# 05.net
KiCad netlist of a schematic drawn in Altium Designer
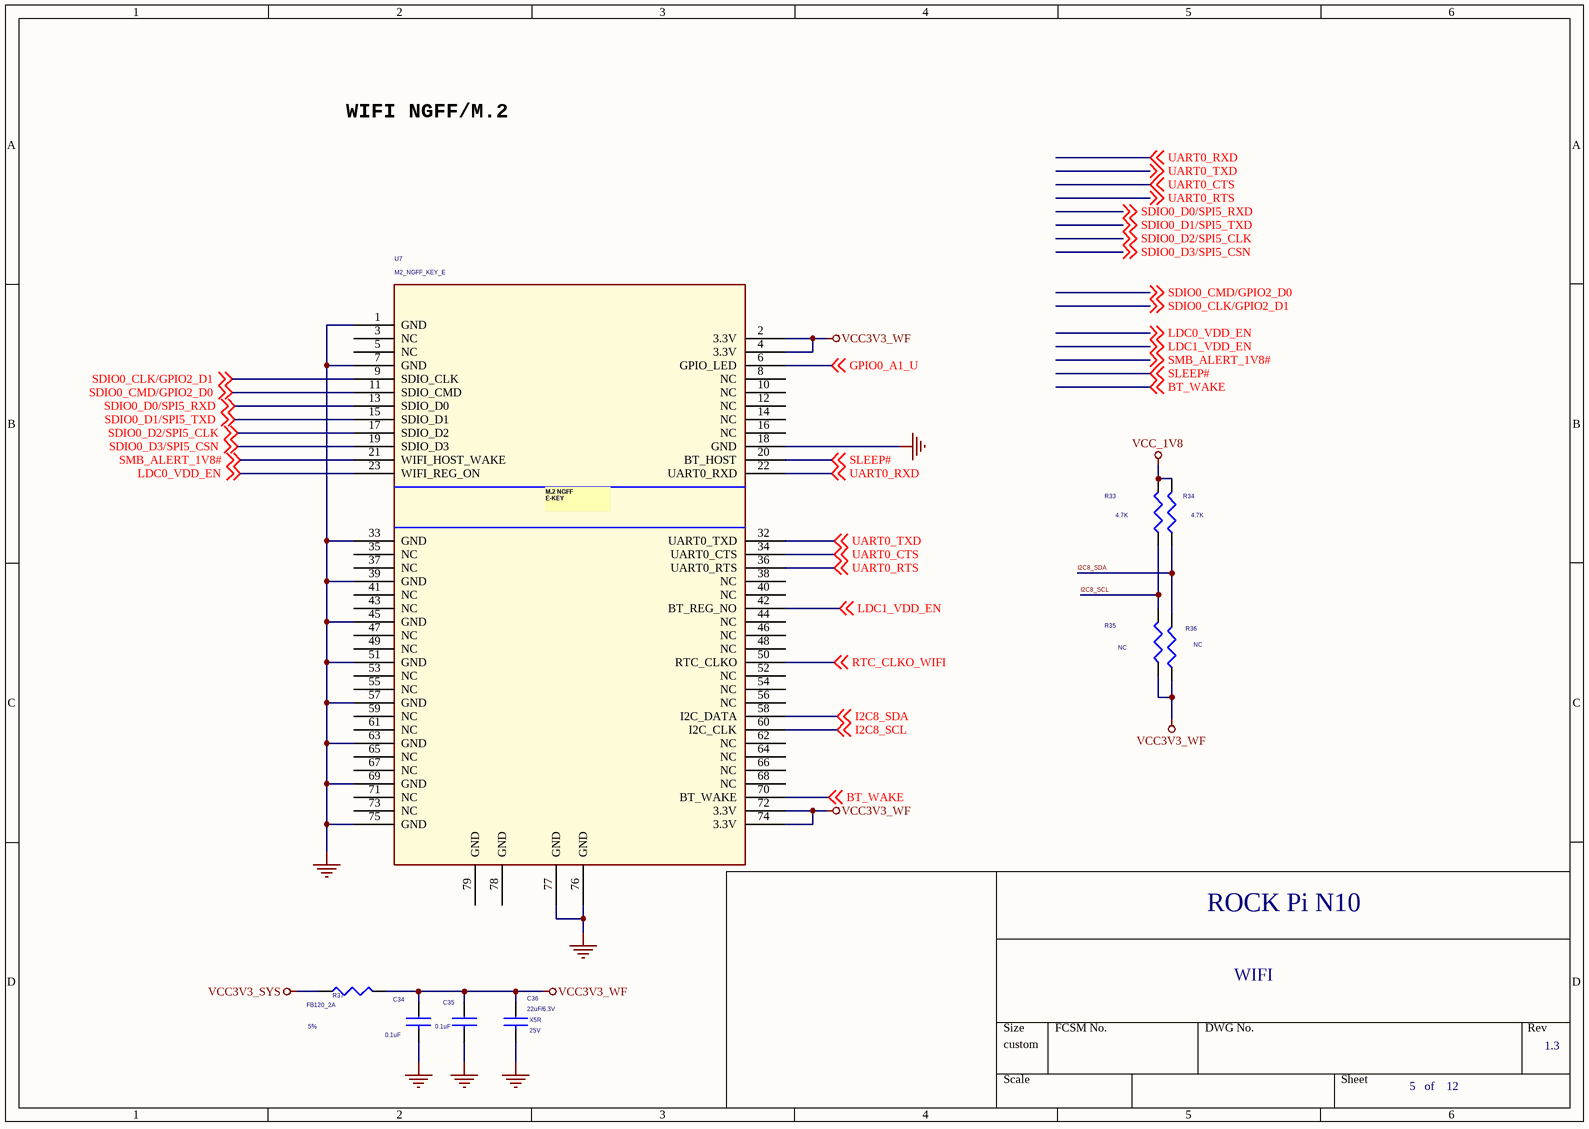
[diagram p0: 05.SchDoc]

(export (version "E")
  (design (tool "Eeschema 10.0.6"))
  (components
    (comp (ref "C34")
      (value "0.1uF")
      (footprint "C0402")
      (description "cap,100.00nF,+/-10%,6.3V,X5R,C0402")
      (fields
        (field (name "VOLTAGE") "16V")
        (field (name "TOLERANCE") "10%")
        (field (name "CREATED BY") "JJJ")
      )
      (libsource (lib "*") (part "CAP NP_2"))
    )
    (comp (ref "C35")
      (value "0.1uF")
      (footprint "C0402")
      (description "cap,100.00nF,+/-10%,6.3V,X5R,C0402")
      (fields
        (field (name "VOLTAGE") "16V")
        (field (name "TOLERANCE") "10%")
        (field (name "CREATED BY") "JJJ")
      )
      (libsource (lib "*") (part "CAP NP_2"))
    )
    (comp (ref "C36")
      (value "22uF/6.3V")
      (footprint "C0805")
      (description "cap,4.70uF,+/-10%,6.3V,X5R,C0603")
      (fields
        (field (name "DIELECTRIC") "X5R")
        (field (name "VOLTAGE") "25V")
        (field (name "MANUFACTURER") "TDK")
        (field (name "TOLERANCE") "10%")
        (field (name "CREATED BY") "JJJ")
      )
      (libsource (lib "*") (part "CAP NP_2"))
    )
    (comp (ref "R33") (value "4.7K") (footprint "R0402") (libsource (lib "*") (part "R_2")))
    (comp (ref "R34") (value "4.7K") (footprint "R0402") (libsource (lib "*") (part "R_2")))
    (comp (ref "R35") (value "NC") (footprint "R0402") (libsource (lib "*") (part "R_2")))
    (comp (ref "R36") (value "NC") (footprint "R0402") (libsource (lib "*") (part "R_2")))
    (comp (ref "R37")
      (value "FB120_2A")
      (footprint "R0402")
      (description "通用厚膜电阻,10K,+/-5%,R0402,1/16W.")
      (fields
        (field (name "TOLERANCE") "5%")
        (field (name "MANUFACTURER") "YAGEO")
        (field (name "CREATED BY") "YTL")
      )
      (libsource (lib "*") (part "RESISTOR_3"))
    )
    (comp (ref "U7")
      (value "M2_NGFF_KEY_E")
      (footprint "M2_NGFF_KEY_E")
      (libsource (lib "*") (part "M_2.2 NGFF EKEY SOCKET"))
    )
  )
  (nets
    (net (code "1") (name "BT_WAKE") (class "Default")
      (node (ref "U7") (pin "70") (pinfunction "BT_WAKE_70") (pintype "passive"))
    )
    (net (code "2") (name "GND") (class "Default")
      (node (ref "C34") (pin "2") (pinfunction "2_2") (pintype "passive"))
      (node (ref "C35") (pin "2") (pinfunction "2_2") (pintype "passive"))
      (node (ref "C36") (pin "2") (pinfunction "2_2") (pintype "passive"))
      (node (ref "U7") (pin "1") (pinfunction "GND_1") (pintype "passive"))
      (node (ref "U7") (pin "18") (pinfunction "GND_18") (pintype "passive"))
      (node (ref "U7") (pin "33") (pinfunction "GND_33") (pintype "passive"))
      (node (ref "U7") (pin "39") (pinfunction "GND_39") (pintype "passive"))
      (node (ref "U7") (pin "45") (pinfunction "GND_45") (pintype "passive"))
      (node (ref "U7") (pin "51") (pinfunction "GND_51") (pintype "passive"))
      (node (ref "U7") (pin "57") (pinfunction "GND_57") (pintype "passive"))
      (node (ref "U7") (pin "63") (pinfunction "GND_63") (pintype "passive"))
      (node (ref "U7") (pin "69") (pinfunction "GND_69") (pintype "passive"))
      (node (ref "U7") (pin "7") (pinfunction "GND_7") (pintype "passive"))
      (node (ref "U7") (pin "75") (pinfunction "GND_75") (pintype "passive"))
      (node (ref "U7") (pin "76") (pinfunction "GND_76") (pintype "passive"))
      (node (ref "U7") (pin "77") (pinfunction "GND_77") (pintype "passive"))
    )
    (net (code "3") (name "GPIO0_A1_U") (class "Default")
      (node (ref "U7") (pin "6") (pinfunction "GPIO_LED_6") (pintype "passive"))
    )
    (net (code "4") (name "I2C8_SCL") (class "Default")
      (node (ref "R33") (pin "1") (pinfunction "1_1") (pintype "passive"))
      (node (ref "R35") (pin "2") (pinfunction "2_2") (pintype "passive"))
      (node (ref "U7") (pin "60") (pinfunction "I2C_CLK_60") (pintype "passive"))
    )
    (net (code "5") (name "I2C8_SDA") (class "Default")
      (node (ref "R34") (pin "1") (pinfunction "1_1") (pintype "passive"))
      (node (ref "R36") (pin "2") (pinfunction "2_2") (pintype "passive"))
      (node (ref "U7") (pin "58") (pinfunction "I2C_DATA_58") (pintype "passive"))
    )
    (net (code "6") (name "LDC0_VDD_EN") (class "Default")
      (node (ref "U7") (pin "23") (pinfunction "WIFI_REG_ON_23") (pintype "passive"))
    )
    (net (code "7") (name "LDC1_VDD_EN") (class "Default")
      (node (ref "U7") (pin "42") (pinfunction "BT_REG_NO_42") (pintype "passive"))
    )
    (net (code "8") (name "RTC_CLKO_WIFI") (class "Default")
      (node (ref "U7") (pin "50") (pinfunction "RTC_CLKO_50") (pintype "passive"))
    )
    (net (code "9") (name "SDIO0_CLK{slash}GPIO2_D1") (class "Default")
      (node (ref "U7") (pin "9") (pinfunction "SDIO_CLK_9") (pintype "passive"))
    )
    (net (code "10") (name "SDIO0_CMD{slash}GPIO2_D0") (class "Default")
      (node (ref "U7") (pin "11") (pinfunction "SDIO_CMD_11") (pintype "passive"))
    )
    (net (code "11") (name "SDIO0_D0{slash}SPI5_RXD") (class "Default")
      (node (ref "U7") (pin "13") (pinfunction "SDIO_D0_13") (pintype "passive"))
    )
    (net (code "12") (name "SDIO0_D1{slash}SPI5_TXD") (class "Default")
      (node (ref "U7") (pin "15") (pinfunction "SDIO_D1_15") (pintype "passive"))
    )
    (net (code "13") (name "SDIO0_D2{slash}SPI5_CLK") (class "Default")
      (node (ref "U7") (pin "17") (pinfunction "SDIO_D2_17") (pintype "passive"))
    )
    (net (code "14") (name "SDIO0_D3{slash}SPI5_CSN") (class "Default")
      (node (ref "U7") (pin "19") (pinfunction "SDIO_D3_19") (pintype "passive"))
    )
    (net (code "15") (name "SLEEP#") (class "Default")
      (node (ref "U7") (pin "20") (pinfunction "BT_HOST_20") (pintype "passive"))
    )
    (net (code "16") (name "SMB_ALERT_1V8#") (class "Default")
      (node (ref "U7") (pin "21") (pinfunction "WIFI_HOST_WAKE_21") (pintype "passive"))
    )
    (net (code "17") (name "UART0_CTS") (class "Default")
      (node (ref "U7") (pin "34") (pinfunction "UART0_CTS_34") (pintype "passive"))
    )
    (net (code "18") (name "UART0_RTS") (class "Default")
      (node (ref "U7") (pin "36") (pinfunction "UART0_RTS_36") (pintype "passive"))
    )
    (net (code "19") (name "UART0_RXD") (class "Default")
      (node (ref "U7") (pin "22") (pinfunction "UART0_RXD_22") (pintype "passive"))
    )
    (net (code "20") (name "UART0_TXD") (class "Default")
      (node (ref "U7") (pin "32") (pinfunction "UART0_TXD_32") (pintype "passive"))
    )
    (net (code "21") (name "VCC3V3_SYS") (class "Default")
      (node (ref "R37") (pin "1") (pinfunction "1_1") (pintype "passive"))
    )
    (net (code "22") (name "VCC3V3_WF") (class "Default")
      (node (ref "C34") (pin "1") (pinfunction "1_1") (pintype "passive"))
      (node (ref "C35") (pin "1") (pinfunction "1_1") (pintype "passive"))
      (node (ref "C36") (pin "1") (pinfunction "1_1") (pintype "passive"))
      (node (ref "R35") (pin "1") (pinfunction "1_1") (pintype "passive"))
      (node (ref "R36") (pin "1") (pinfunction "1_1") (pintype "passive"))
      (node (ref "R37") (pin "2") (pinfunction "2_2") (pintype "passive"))
      (node (ref "U7") (pin "2") (pinfunction "3.3V_2") (pintype "passive"))
      (node (ref "U7") (pin "4") (pinfunction "3.3V_4") (pintype "passive"))
      (node (ref "U7") (pin "72") (pinfunction "3.3V_72") (pintype "passive"))
      (node (ref "U7") (pin "74") (pinfunction "3.3V_74") (pintype "passive"))
    )
    (net (code "23") (name "VCC_1V8") (class "Default")
      (node (ref "R33") (pin "2") (pinfunction "2_2") (pintype "passive"))
      (node (ref "R34") (pin "2") (pinfunction "2_2") (pintype "passive"))
    )
    (net (code "24") (name "unconnected-(U7-GND-Pad78)") (class "Default")
      (node (ref "U7") (pin "78") (pinfunction "GND_78") (pintype "passive"))
    )
    (net (code "25") (name "unconnected-(U7-GND-Pad79)") (class "Default")
      (node (ref "U7") (pin "79") (pinfunction "GND_79") (pintype "passive"))
    )
    (net (code "26") (name "unconnected-(U7-NC-Pad3)") (class "Default")
      (node (ref "U7") (pin "3") (pinfunction "NC_3") (pintype "passive"))
    )
    (net (code "27") (name "unconnected-(U7-NC-Pad5)") (class "Default")
      (node (ref "U7") (pin "5") (pinfunction "NC_5") (pintype "passive"))
    )
    (net (code "28") (name "unconnected-(U7-NC-Pad8)") (class "Default")
      (node (ref "U7") (pin "8") (pinfunction "NC_8") (pintype "passive"))
    )
    (net (code "29") (name "unconnected-(U7-NC-Pad10)") (class "Default")
      (node (ref "U7") (pin "10") (pinfunction "NC_10") (pintype "passive"))
    )
    (net (code "30") (name "unconnected-(U7-NC-Pad12)") (class "Default")
      (node (ref "U7") (pin "12") (pinfunction "NC_12") (pintype "passive"))
    )
    (net (code "31") (name "unconnected-(U7-NC-Pad14)") (class "Default")
      (node (ref "U7") (pin "14") (pinfunction "NC_14") (pintype "passive"))
    )
    (net (code "32") (name "unconnected-(U7-NC-Pad16)") (class "Default")
      (node (ref "U7") (pin "16") (pinfunction "NC_16") (pintype "passive"))
    )
    (net (code "33") (name "unconnected-(U7-NC-Pad35)") (class "Default")
      (node (ref "U7") (pin "35") (pinfunction "NC_35") (pintype "passive"))
    )
    (net (code "34") (name "unconnected-(U7-NC-Pad37)") (class "Default")
      (node (ref "U7") (pin "37") (pinfunction "NC_37") (pintype "passive"))
    )
    (net (code "35") (name "unconnected-(U7-NC-Pad38)") (class "Default")
      (node (ref "U7") (pin "38") (pinfunction "NC_38") (pintype "passive"))
    )
    (net (code "36") (name "unconnected-(U7-NC-Pad40)") (class "Default")
      (node (ref "U7") (pin "40") (pinfunction "NC_40") (pintype "passive"))
    )
    (net (code "37") (name "unconnected-(U7-NC-Pad41)") (class "Default")
      (node (ref "U7") (pin "41") (pinfunction "NC_41") (pintype "passive"))
    )
    (net (code "38") (name "unconnected-(U7-NC-Pad43)") (class "Default")
      (node (ref "U7") (pin "43") (pinfunction "NC_43") (pintype "passive"))
    )
    (net (code "39") (name "unconnected-(U7-NC-Pad44)") (class "Default")
      (node (ref "U7") (pin "44") (pinfunction "NC_44") (pintype "passive"))
    )
    (net (code "40") (name "unconnected-(U7-NC-Pad46)") (class "Default")
      (node (ref "U7") (pin "46") (pinfunction "NC_46") (pintype "passive"))
    )
    (net (code "41") (name "unconnected-(U7-NC-Pad47)") (class "Default")
      (node (ref "U7") (pin "47") (pinfunction "NC_47") (pintype "passive"))
    )
    (net (code "42") (name "unconnected-(U7-NC-Pad48)") (class "Default")
      (node (ref "U7") (pin "48") (pinfunction "NC_48") (pintype "passive"))
    )
    (net (code "43") (name "unconnected-(U7-NC-Pad49)") (class "Default")
      (node (ref "U7") (pin "49") (pinfunction "NC_49") (pintype "passive"))
    )
    (net (code "44") (name "unconnected-(U7-NC-Pad52)") (class "Default")
      (node (ref "U7") (pin "52") (pinfunction "NC_52") (pintype "passive"))
    )
    (net (code "45") (name "unconnected-(U7-NC-Pad53)") (class "Default")
      (node (ref "U7") (pin "53") (pinfunction "NC_53") (pintype "passive"))
    )
    (net (code "46") (name "unconnected-(U7-NC-Pad54)") (class "Default")
      (node (ref "U7") (pin "54") (pinfunction "NC_54") (pintype "passive"))
    )
    (net (code "47") (name "unconnected-(U7-NC-Pad55)") (class "Default")
      (node (ref "U7") (pin "55") (pinfunction "NC_55") (pintype "passive"))
    )
    (net (code "48") (name "unconnected-(U7-NC-Pad56)") (class "Default")
      (node (ref "U7") (pin "56") (pinfunction "NC_56") (pintype "passive"))
    )
    (net (code "49") (name "unconnected-(U7-NC-Pad59)") (class "Default")
      (node (ref "U7") (pin "59") (pinfunction "NC_59") (pintype "passive"))
    )
    (net (code "50") (name "unconnected-(U7-NC-Pad61)") (class "Default")
      (node (ref "U7") (pin "61") (pinfunction "NC_61") (pintype "passive"))
    )
    (net (code "51") (name "unconnected-(U7-NC-Pad62)") (class "Default")
      (node (ref "U7") (pin "62") (pinfunction "NC_62") (pintype "passive"))
    )
    (net (code "52") (name "unconnected-(U7-NC-Pad64)") (class "Default")
      (node (ref "U7") (pin "64") (pinfunction "NC_64") (pintype "passive"))
    )
    (net (code "53") (name "unconnected-(U7-NC-Pad65)") (class "Default")
      (node (ref "U7") (pin "65") (pinfunction "NC_65") (pintype "passive"))
    )
    (net (code "54") (name "unconnected-(U7-NC-Pad66)") (class "Default")
      (node (ref "U7") (pin "66") (pinfunction "NC_66") (pintype "passive"))
    )
    (net (code "55") (name "unconnected-(U7-NC-Pad67)") (class "Default")
      (node (ref "U7") (pin "67") (pinfunction "NC_67") (pintype "passive"))
    )
    (net (code "56") (name "unconnected-(U7-NC-Pad68)") (class "Default")
      (node (ref "U7") (pin "68") (pinfunction "NC_68") (pintype "passive"))
    )
    (net (code "57") (name "unconnected-(U7-NC-Pad71)") (class "Default")
      (node (ref "U7") (pin "71") (pinfunction "NC_71") (pintype "passive"))
    )
    (net (code "58") (name "unconnected-(U7-NC-Pad73)") (class "Default")
      (node (ref "U7") (pin "73") (pinfunction "NC_73") (pintype "passive"))
    )
  )
)
